# quartzGenerator.net
KiCad netlist of a schematic drawn in EAGLE
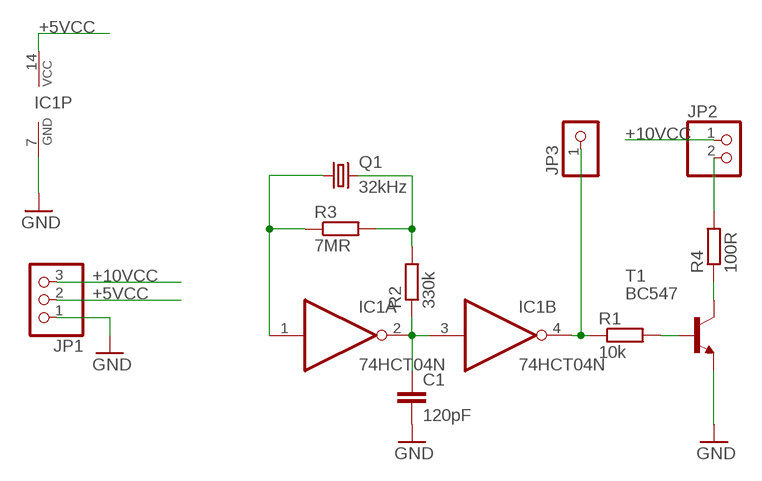
[diagram p0: schematic, sheet 1]

(export (version "E")
  (design (tool "Eeschema 10.0.6"))
  (components
    (comp (ref "C1")
      (value "120pF")
      (footprint "eagle-import:C050-030X075")
      (libsource (lib "eagle-import") (part "C-EU050-030X075"))
    )
    (comp (ref "IC1")
      (value "74HCT04N")
      (footprint "eagle-import:DIL14")
      (libsource (lib "eagle-import") (part "7404NHCT"))
    )
    (comp (ref "JP1")
      (value "PINHD-1X3")
      (footprint "eagle-import:1X03")
      (libsource (lib "eagle-import") (part "PINHD-1X3"))
    )
    (comp (ref "JP2")
      (value "PINHD-1X2")
      (footprint "eagle-import:1X02")
      (libsource (lib "eagle-import") (part "PINHD-1X2"))
    )
    (comp (ref "JP3")
      (value "PINHD-1X1")
      (footprint "eagle-import:1X01")
      (libsource (lib "eagle-import") (part "PINHD-1X1"))
    )
    (comp (ref "Q1")
      (value "32kHz")
      (footprint "eagle-import:TC26H")
      (libsource (lib "eagle-import") (part "CRYSTALTC26H"))
    )
    (comp (ref "R1")
      (value "10k")
      (footprint "eagle-import:0207_7")
      (libsource (lib "eagle-import") (part "R-EU_0207/7"))
    )
    (comp (ref "R2")
      (value "330k")
      (footprint "eagle-import:0207_7")
      (libsource (lib "eagle-import") (part "R-EU_0207/7"))
    )
    (comp (ref "R3")
      (value "7MR")
      (footprint "eagle-import:0207_7")
      (libsource (lib "eagle-import") (part "R-EU_0207/7"))
    )
    (comp (ref "R4")
      (value "100R")
      (footprint "eagle-import:0207_7")
      (libsource (lib "eagle-import") (part "R-EU_0207/7"))
    )
    (comp (ref "T1")
      (value "BC547")
      (footprint "eagle-import:TO92")
      (libsource (lib "eagle-import") (part "BC547"))
    )
  )
  (nets
    (net (code "1") (name "/+5VCC") (class "Default")
      (node (ref "IC1") (pin "14") (pinfunction "VCC_14") (pintype "power_in"))
      (node (ref "JP1") (pin "2") (pinfunction "2_2") (pintype "passive"))
    )
    (net (code "2") (name "/+10VCC") (class "Default")
      (node (ref "JP1") (pin "3") (pinfunction "3_3") (pintype "passive"))
      (node (ref "JP2") (pin "1") (pinfunction "1_1") (pintype "passive"))
    )
    (net (code "3") (name "GND") (class "Default")
      (node (ref "C1") (pin "2") (pinfunction "2_2") (pintype "passive"))
      (node (ref "IC1") (pin "7") (pinfunction "GND_7") (pintype "power_in"))
      (node (ref "JP1") (pin "1") (pinfunction "1_1") (pintype "passive"))
      (node (ref "T1") (pin "1") (pinfunction "E_1") (pintype "passive"))
    )
    (net (code "4") (name "Net-(IC1A-I)") (class "Default")
      (node (ref "IC1") (pin "1") (pinfunction "I_1") (pintype "input"))
      (node (ref "Q1") (pin "1") (pinfunction "1_1") (pintype "passive"))
      (node (ref "R3") (pin "1") (pinfunction "1_1") (pintype "passive"))
    )
    (net (code "5") (name "Net-(IC1A-O)") (class "Default")
      (node (ref "C1") (pin "1") (pinfunction "1_1") (pintype "passive"))
      (node (ref "IC1") (pin "2") (pinfunction "O_2") (pintype "output"))
      (node (ref "IC1") (pin "3") (pinfunction "I_3") (pintype "input"))
      (node (ref "R2") (pin "1") (pinfunction "1_1") (pintype "passive"))
    )
    (net (code "6") (name "Net-(IC1B-O)") (class "Default")
      (node (ref "IC1") (pin "4") (pinfunction "O_4") (pintype "output"))
      (node (ref "JP3") (pin "1") (pinfunction "1_1") (pintype "passive"))
      (node (ref "R1") (pin "1") (pinfunction "1_1") (pintype "passive"))
    )
    (net (code "7") (name "Net-(JP2-Pad2)") (class "Default")
      (node (ref "JP2") (pin "2") (pinfunction "2_2") (pintype "passive"))
      (node (ref "R4") (pin "2") (pinfunction "2_2") (pintype "passive"))
    )
    (net (code "8") (name "Net-(Q1-Pad2)") (class "Default")
      (node (ref "Q1") (pin "2") (pinfunction "2_2") (pintype "passive"))
      (node (ref "R2") (pin "2") (pinfunction "2_2") (pintype "passive"))
      (node (ref "R3") (pin "2") (pinfunction "2_2") (pintype "passive"))
    )
    (net (code "9") (name "Net-(T1-B)") (class "Default")
      (node (ref "R1") (pin "2") (pinfunction "2_2") (pintype "passive"))
      (node (ref "T1") (pin "2") (pinfunction "B_2") (pintype "passive"))
    )
    (net (code "10") (name "Net-(T1-C)") (class "Default")
      (node (ref "R4") (pin "1") (pinfunction "1_1") (pintype "passive"))
      (node (ref "T1") (pin "3") (pinfunction "C_3") (pintype "passive"))
    )
  )
)
